# PGTNX06_ioexpander.net
KiCad netlist of a schematic drawn in EAGLE
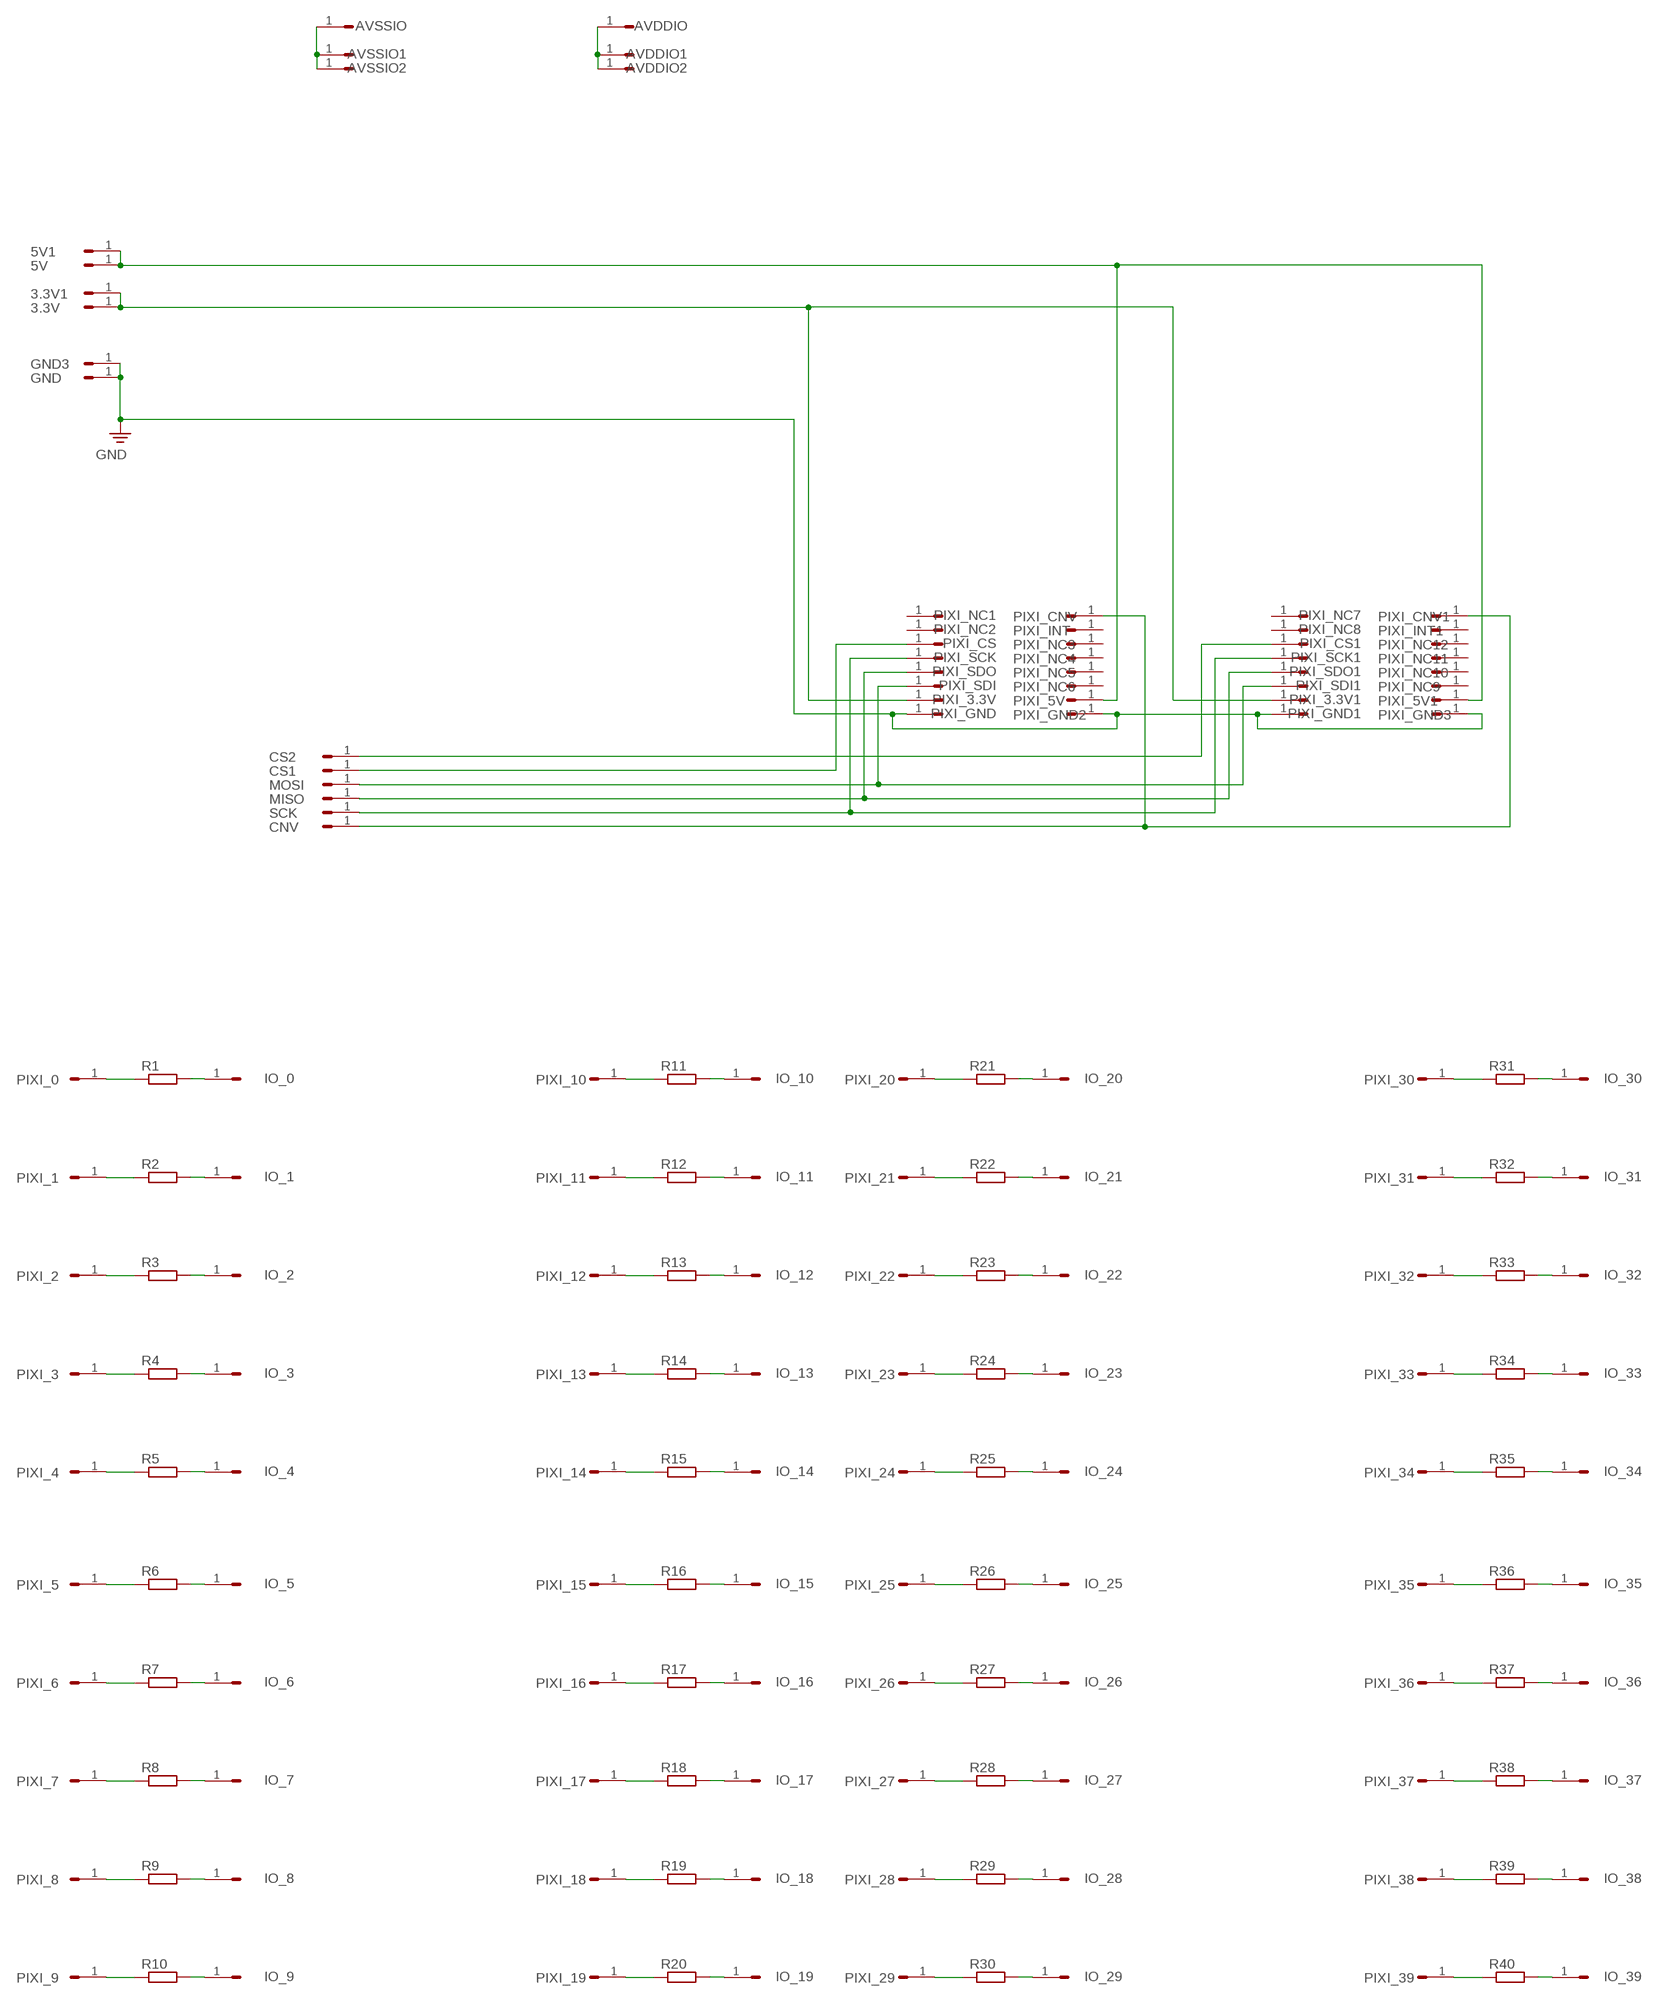
[diagram p0: schematic, sheet 1]

(export (version "E")
  (design (tool "Eeschema 10.0.6"))
  (components
    (comp (ref "3.3V")
      (value "HEADER/MALE/01")
      (footprint "eagle-import:HEADER_MALE_01")
      (fields (field (name "SPICEPREFIX") "X"))
      (libsource (lib "eagle-import") (part "HEADER/MALE/01"))
    )
    (comp (ref "3.3V1")
      (value "HEADER/MALE/01")
      (footprint "eagle-import:HEADER_MALE_01")
      (fields (field (name "SPICEPREFIX") "X"))
      (libsource (lib "eagle-import") (part "HEADER/MALE/01"))
    )
    (comp (ref "5V")
      (value "HEADER/MALE/01")
      (footprint "eagle-import:HEADER_MALE_01")
      (fields (field (name "SPICEPREFIX") "X"))
      (libsource (lib "eagle-import") (part "HEADER/MALE/01"))
    )
    (comp (ref "5V1")
      (value "HEADER/MALE/01")
      (footprint "eagle-import:HEADER_MALE_01")
      (fields (field (name "SPICEPREFIX") "X"))
      (libsource (lib "eagle-import") (part "HEADER/MALE/01"))
    )
    (comp (ref "AVDDIO")
      (value "HEADER/MALE/01")
      (footprint "eagle-import:HEADER_MALE_01")
      (fields (field (name "SPICEPREFIX") "X"))
      (libsource (lib "eagle-import") (part "HEADER/MALE/01"))
    )
    (comp (ref "AVDDIO1")
      (value "HEADER/MALE/01")
      (footprint "eagle-import:HEADER_MALE_01")
      (fields (field (name "SPICEPREFIX") "X"))
      (libsource (lib "eagle-import") (part "HEADER/MALE/01"))
    )
    (comp (ref "AVDDIO2")
      (value "HEADER/MALE/01")
      (footprint "eagle-import:HEADER_MALE_01")
      (fields (field (name "SPICEPREFIX") "X"))
      (libsource (lib "eagle-import") (part "HEADER/MALE/01"))
    )
    (comp (ref "AVSSIO")
      (value "HEADER/MALE/01")
      (footprint "eagle-import:HEADER_MALE_01")
      (fields (field (name "SPICEPREFIX") "X"))
      (libsource (lib "eagle-import") (part "HEADER/MALE/01"))
    )
    (comp (ref "AVSSIO1")
      (value "HEADER/MALE/01")
      (footprint "eagle-import:HEADER_MALE_01")
      (fields (field (name "SPICEPREFIX") "X"))
      (libsource (lib "eagle-import") (part "HEADER/MALE/01"))
    )
    (comp (ref "AVSSIO2")
      (value "HEADER/MALE/01")
      (footprint "eagle-import:HEADER_MALE_01")
      (fields (field (name "SPICEPREFIX") "X"))
      (libsource (lib "eagle-import") (part "HEADER/MALE/01"))
    )
    (comp (ref "CNV")
      (value "HEADER/MALE/01")
      (footprint "eagle-import:HEADER_MALE_01")
      (fields (field (name "SPICEPREFIX") "X"))
      (libsource (lib "eagle-import") (part "HEADER/MALE/01"))
    )
    (comp (ref "CS1")
      (value "HEADER/MALE/01")
      (footprint "eagle-import:HEADER_MALE_01")
      (fields (field (name "SPICEPREFIX") "X"))
      (libsource (lib "eagle-import") (part "HEADER/MALE/01"))
    )
    (comp (ref "CS2")
      (value "HEADER/MALE/01")
      (footprint "eagle-import:HEADER_MALE_01")
      (fields (field (name "SPICEPREFIX") "X"))
      (libsource (lib "eagle-import") (part "HEADER/MALE/01"))
    )
    (comp (ref "GND")
      (value "HEADER/MALE/01")
      (footprint "eagle-import:HEADER_MALE_01")
      (fields (field (name "SPICEPREFIX") "X"))
      (libsource (lib "eagle-import") (part "HEADER/MALE/01"))
    )
    (comp (ref "GND3")
      (value "HEADER/MALE/01")
      (footprint "eagle-import:HEADER_MALE_01")
      (fields (field (name "SPICEPREFIX") "X"))
      (libsource (lib "eagle-import") (part "HEADER/MALE/01"))
    )
    (comp (ref "IO_0")
      (value "HEADER/MALE/01")
      (footprint "eagle-import:HEADER_MALE_01")
      (fields (field (name "SPICEPREFIX") "X"))
      (libsource (lib "eagle-import") (part "HEADER/MALE/01"))
    )
    (comp (ref "IO_1")
      (value "HEADER/MALE/01")
      (footprint "eagle-import:HEADER_MALE_01")
      (fields (field (name "SPICEPREFIX") "X"))
      (libsource (lib "eagle-import") (part "HEADER/MALE/01"))
    )
    (comp (ref "IO_2")
      (value "HEADER/MALE/01")
      (footprint "eagle-import:HEADER_MALE_01")
      (fields (field (name "SPICEPREFIX") "X"))
      (libsource (lib "eagle-import") (part "HEADER/MALE/01"))
    )
    (comp (ref "IO_3")
      (value "HEADER/MALE/01")
      (footprint "eagle-import:HEADER_MALE_01")
      (fields (field (name "SPICEPREFIX") "X"))
      (libsource (lib "eagle-import") (part "HEADER/MALE/01"))
    )
    (comp (ref "IO_4")
      (value "HEADER/MALE/01")
      (footprint "eagle-import:HEADER_MALE_01")
      (fields (field (name "SPICEPREFIX") "X"))
      (libsource (lib "eagle-import") (part "HEADER/MALE/01"))
    )
    (comp (ref "IO_5")
      (value "HEADER/MALE/01")
      (footprint "eagle-import:HEADER_MALE_01")
      (fields (field (name "SPICEPREFIX") "X"))
      (libsource (lib "eagle-import") (part "HEADER/MALE/01"))
    )
    (comp (ref "IO_6")
      (value "HEADER/MALE/01")
      (footprint "eagle-import:HEADER_MALE_01")
      (fields (field (name "SPICEPREFIX") "X"))
      (libsource (lib "eagle-import") (part "HEADER/MALE/01"))
    )
    (comp (ref "IO_7")
      (value "HEADER/MALE/01")
      (footprint "eagle-import:HEADER_MALE_01")
      (fields (field (name "SPICEPREFIX") "X"))
      (libsource (lib "eagle-import") (part "HEADER/MALE/01"))
    )
    (comp (ref "IO_8")
      (value "HEADER/MALE/01")
      (footprint "eagle-import:HEADER_MALE_01")
      (fields (field (name "SPICEPREFIX") "X"))
      (libsource (lib "eagle-import") (part "HEADER/MALE/01"))
    )
    (comp (ref "IO_9")
      (value "HEADER/MALE/01")
      (footprint "eagle-import:HEADER_MALE_01")
      (fields (field (name "SPICEPREFIX") "X"))
      (libsource (lib "eagle-import") (part "HEADER/MALE/01"))
    )
    (comp (ref "IO_10")
      (value "HEADER/MALE/01")
      (footprint "eagle-import:HEADER_MALE_01")
      (fields (field (name "SPICEPREFIX") "X"))
      (libsource (lib "eagle-import") (part "HEADER/MALE/01"))
    )
    (comp (ref "IO_11")
      (value "HEADER/MALE/01")
      (footprint "eagle-import:HEADER_MALE_01")
      (fields (field (name "SPICEPREFIX") "X"))
      (libsource (lib "eagle-import") (part "HEADER/MALE/01"))
    )
    (comp (ref "IO_12")
      (value "HEADER/MALE/01")
      (footprint "eagle-import:HEADER_MALE_01")
      (fields (field (name "SPICEPREFIX") "X"))
      (libsource (lib "eagle-import") (part "HEADER/MALE/01"))
    )
    (comp (ref "IO_13")
      (value "HEADER/MALE/01")
      (footprint "eagle-import:HEADER_MALE_01")
      (fields (field (name "SPICEPREFIX") "X"))
      (libsource (lib "eagle-import") (part "HEADER/MALE/01"))
    )
    (comp (ref "IO_14")
      (value "HEADER/MALE/01")
      (footprint "eagle-import:HEADER_MALE_01")
      (fields (field (name "SPICEPREFIX") "X"))
      (libsource (lib "eagle-import") (part "HEADER/MALE/01"))
    )
    (comp (ref "IO_15")
      (value "HEADER/MALE/01")
      (footprint "eagle-import:HEADER_MALE_01")
      (fields (field (name "SPICEPREFIX") "X"))
      (libsource (lib "eagle-import") (part "HEADER/MALE/01"))
    )
    (comp (ref "IO_16")
      (value "HEADER/MALE/01")
      (footprint "eagle-import:HEADER_MALE_01")
      (fields (field (name "SPICEPREFIX") "X"))
      (libsource (lib "eagle-import") (part "HEADER/MALE/01"))
    )
    (comp (ref "IO_17")
      (value "HEADER/MALE/01")
      (footprint "eagle-import:HEADER_MALE_01")
      (fields (field (name "SPICEPREFIX") "X"))
      (libsource (lib "eagle-import") (part "HEADER/MALE/01"))
    )
    (comp (ref "IO_18")
      (value "HEADER/MALE/01")
      (footprint "eagle-import:HEADER_MALE_01")
      (fields (field (name "SPICEPREFIX") "X"))
      (libsource (lib "eagle-import") (part "HEADER/MALE/01"))
    )
    (comp (ref "IO_19")
      (value "HEADER/MALE/01")
      (footprint "eagle-import:HEADER_MALE_01")
      (fields (field (name "SPICEPREFIX") "X"))
      (libsource (lib "eagle-import") (part "HEADER/MALE/01"))
    )
    (comp (ref "IO_20")
      (value "HEADER/MALE/01")
      (footprint "eagle-import:HEADER_MALE_01")
      (fields (field (name "SPICEPREFIX") "X"))
      (libsource (lib "eagle-import") (part "HEADER/MALE/01"))
    )
    (comp (ref "IO_21")
      (value "HEADER/MALE/01")
      (footprint "eagle-import:HEADER_MALE_01")
      (fields (field (name "SPICEPREFIX") "X"))
      (libsource (lib "eagle-import") (part "HEADER/MALE/01"))
    )
    (comp (ref "IO_22")
      (value "HEADER/MALE/01")
      (footprint "eagle-import:HEADER_MALE_01")
      (fields (field (name "SPICEPREFIX") "X"))
      (libsource (lib "eagle-import") (part "HEADER/MALE/01"))
    )
    (comp (ref "IO_23")
      (value "HEADER/MALE/01")
      (footprint "eagle-import:HEADER_MALE_01")
      (fields (field (name "SPICEPREFIX") "X"))
      (libsource (lib "eagle-import") (part "HEADER/MALE/01"))
    )
    (comp (ref "IO_24")
      (value "HEADER/MALE/01")
      (footprint "eagle-import:HEADER_MALE_01")
      (fields (field (name "SPICEPREFIX") "X"))
      (libsource (lib "eagle-import") (part "HEADER/MALE/01"))
    )
    (comp (ref "IO_25")
      (value "HEADER/MALE/01")
      (footprint "eagle-import:HEADER_MALE_01")
      (fields (field (name "SPICEPREFIX") "X"))
      (libsource (lib "eagle-import") (part "HEADER/MALE/01"))
    )
    (comp (ref "IO_26")
      (value "HEADER/MALE/01")
      (footprint "eagle-import:HEADER_MALE_01")
      (fields (field (name "SPICEPREFIX") "X"))
      (libsource (lib "eagle-import") (part "HEADER/MALE/01"))
    )
    (comp (ref "IO_27")
      (value "HEADER/MALE/01")
      (footprint "eagle-import:HEADER_MALE_01")
      (fields (field (name "SPICEPREFIX") "X"))
      (libsource (lib "eagle-import") (part "HEADER/MALE/01"))
    )
    (comp (ref "IO_28")
      (value "HEADER/MALE/01")
      (footprint "eagle-import:HEADER_MALE_01")
      (fields (field (name "SPICEPREFIX") "X"))
      (libsource (lib "eagle-import") (part "HEADER/MALE/01"))
    )
    (comp (ref "IO_29")
      (value "HEADER/MALE/01")
      (footprint "eagle-import:HEADER_MALE_01")
      (fields (field (name "SPICEPREFIX") "X"))
      (libsource (lib "eagle-import") (part "HEADER/MALE/01"))
    )
    (comp (ref "IO_30")
      (value "HEADER/MALE/01")
      (footprint "eagle-import:HEADER_MALE_01")
      (fields (field (name "SPICEPREFIX") "X"))
      (libsource (lib "eagle-import") (part "HEADER/MALE/01"))
    )
    (comp (ref "IO_31")
      (value "HEADER/MALE/01")
      (footprint "eagle-import:HEADER_MALE_01")
      (fields (field (name "SPICEPREFIX") "X"))
      (libsource (lib "eagle-import") (part "HEADER/MALE/01"))
    )
    (comp (ref "IO_32")
      (value "HEADER/MALE/01")
      (footprint "eagle-import:HEADER_MALE_01")
      (fields (field (name "SPICEPREFIX") "X"))
      (libsource (lib "eagle-import") (part "HEADER/MALE/01"))
    )
    (comp (ref "IO_33")
      (value "HEADER/MALE/01")
      (footprint "eagle-import:HEADER_MALE_01")
      (fields (field (name "SPICEPREFIX") "X"))
      (libsource (lib "eagle-import") (part "HEADER/MALE/01"))
    )
    (comp (ref "IO_34")
      (value "HEADER/MALE/01")
      (footprint "eagle-import:HEADER_MALE_01")
      (fields (field (name "SPICEPREFIX") "X"))
      (libsource (lib "eagle-import") (part "HEADER/MALE/01"))
    )
    (comp (ref "IO_35")
      (value "HEADER/MALE/01")
      (footprint "eagle-import:HEADER_MALE_01")
      (fields (field (name "SPICEPREFIX") "X"))
      (libsource (lib "eagle-import") (part "HEADER/MALE/01"))
    )
    (comp (ref "IO_36")
      (value "HEADER/MALE/01")
      (footprint "eagle-import:HEADER_MALE_01")
      (fields (field (name "SPICEPREFIX") "X"))
      (libsource (lib "eagle-import") (part "HEADER/MALE/01"))
    )
    (comp (ref "IO_37")
      (value "HEADER/MALE/01")
      (footprint "eagle-import:HEADER_MALE_01")
      (fields (field (name "SPICEPREFIX") "X"))
      (libsource (lib "eagle-import") (part "HEADER/MALE/01"))
    )
    (comp (ref "IO_38")
      (value "HEADER/MALE/01")
      (footprint "eagle-import:HEADER_MALE_01")
      (fields (field (name "SPICEPREFIX") "X"))
      (libsource (lib "eagle-import") (part "HEADER/MALE/01"))
    )
    (comp (ref "IO_39")
      (value "HEADER/MALE/01")
      (footprint "eagle-import:HEADER_MALE_01")
      (fields (field (name "SPICEPREFIX") "X"))
      (libsource (lib "eagle-import") (part "HEADER/MALE/01"))
    )
    (comp (ref "MISO")
      (value "HEADER/MALE/01")
      (footprint "eagle-import:HEADER_MALE_01")
      (fields (field (name "SPICEPREFIX") "X"))
      (libsource (lib "eagle-import") (part "HEADER/MALE/01"))
    )
    (comp (ref "MOSI")
      (value "HEADER/MALE/01")
      (footprint "eagle-import:HEADER_MALE_01")
      (fields (field (name "SPICEPREFIX") "X"))
      (libsource (lib "eagle-import") (part "HEADER/MALE/01"))
    )
    (comp (ref "PIXI_0")
      (value "HEADER/MALE/01")
      (footprint "eagle-import:HEADER_MALE_01")
      (fields (field (name "SPICEPREFIX") "X"))
      (libsource (lib "eagle-import") (part "HEADER/MALE/01"))
    )
    (comp (ref "PIXI_1")
      (value "HEADER/MALE/01")
      (footprint "eagle-import:HEADER_MALE_01")
      (fields (field (name "SPICEPREFIX") "X"))
      (libsource (lib "eagle-import") (part "HEADER/MALE/01"))
    )
    (comp (ref "PIXI_2")
      (value "HEADER/MALE/01")
      (footprint "eagle-import:HEADER_MALE_01")
      (fields (field (name "SPICEPREFIX") "X"))
      (libsource (lib "eagle-import") (part "HEADER/MALE/01"))
    )
    (comp (ref "PIXI_3")
      (value "HEADER/MALE/01")
      (footprint "eagle-import:HEADER_MALE_01")
      (fields (field (name "SPICEPREFIX") "X"))
      (libsource (lib "eagle-import") (part "HEADER/MALE/01"))
    )
    (comp (ref "PIXI_3.3V")
      (value "HEADER/MALE/01")
      (footprint "eagle-import:HEADER_MALE_01")
      (fields (field (name "SPICEPREFIX") "X"))
      (libsource (lib "eagle-import") (part "HEADER/MALE/01"))
    )
    (comp (ref "PIXI_3.3V1")
      (value "HEADER/MALE/01")
      (footprint "eagle-import:HEADER_MALE_01")
      (fields (field (name "SPICEPREFIX") "X"))
      (libsource (lib "eagle-import") (part "HEADER/MALE/01"))
    )
    (comp (ref "PIXI_4")
      (value "HEADER/MALE/01")
      (footprint "eagle-import:HEADER_MALE_01")
      (fields (field (name "SPICEPREFIX") "X"))
      (libsource (lib "eagle-import") (part "HEADER/MALE/01"))
    )
    (comp (ref "PIXI_5")
      (value "HEADER/MALE/01")
      (footprint "eagle-import:HEADER_MALE_01")
      (fields (field (name "SPICEPREFIX") "X"))
      (libsource (lib "eagle-import") (part "HEADER/MALE/01"))
    )
    (comp (ref "PIXI_5V")
      (value "HEADER/MALE/01")
      (footprint "eagle-import:HEADER_MALE_01")
      (fields (field (name "SPICEPREFIX") "X"))
      (libsource (lib "eagle-import") (part "HEADER/MALE/01"))
    )
    (comp (ref "PIXI_5V1")
      (value "HEADER/MALE/01")
      (footprint "eagle-import:HEADER_MALE_01")
      (fields (field (name "SPICEPREFIX") "X"))
      (libsource (lib "eagle-import") (part "HEADER/MALE/01"))
    )
    (comp (ref "PIXI_6")
      (value "HEADER/MALE/01")
      (footprint "eagle-import:HEADER_MALE_01")
      (fields (field (name "SPICEPREFIX") "X"))
      (libsource (lib "eagle-import") (part "HEADER/MALE/01"))
    )
    (comp (ref "PIXI_7")
      (value "HEADER/MALE/01")
      (footprint "eagle-import:HEADER_MALE_01")
      (fields (field (name "SPICEPREFIX") "X"))
      (libsource (lib "eagle-import") (part "HEADER/MALE/01"))
    )
    (comp (ref "PIXI_8")
      (value "HEADER/MALE/01")
      (footprint "eagle-import:HEADER_MALE_01")
      (fields (field (name "SPICEPREFIX") "X"))
      (libsource (lib "eagle-import") (part "HEADER/MALE/01"))
    )
    (comp (ref "PIXI_9")
      (value "HEADER/MALE/01")
      (footprint "eagle-import:HEADER_MALE_01")
      (fields (field (name "SPICEPREFIX") "X"))
      (libsource (lib "eagle-import") (part "HEADER/MALE/01"))
    )
    (comp (ref "PIXI_10")
      (value "HEADER/MALE/01")
      (footprint "eagle-import:HEADER_MALE_01")
      (fields (field (name "SPICEPREFIX") "X"))
      (libsource (lib "eagle-import") (part "HEADER/MALE/01"))
    )
    (comp (ref "PIXI_11")
      (value "HEADER/MALE/01")
      (footprint "eagle-import:HEADER_MALE_01")
      (fields (field (name "SPICEPREFIX") "X"))
      (libsource (lib "eagle-import") (part "HEADER/MALE/01"))
    )
    (comp (ref "PIXI_12")
      (value "HEADER/MALE/01")
      (footprint "eagle-import:HEADER_MALE_01")
      (fields (field (name "SPICEPREFIX") "X"))
      (libsource (lib "eagle-import") (part "HEADER/MALE/01"))
    )
    (comp (ref "PIXI_13")
      (value "HEADER/MALE/01")
      (footprint "eagle-import:HEADER_MALE_01")
      (fields (field (name "SPICEPREFIX") "X"))
      (libsource (lib "eagle-import") (part "HEADER/MALE/01"))
    )
    (comp (ref "PIXI_14")
      (value "HEADER/MALE/01")
      (footprint "eagle-import:HEADER_MALE_01")
      (fields (field (name "SPICEPREFIX") "X"))
      (libsource (lib "eagle-import") (part "HEADER/MALE/01"))
    )
    (comp (ref "PIXI_15")
      (value "HEADER/MALE/01")
      (footprint "eagle-import:HEADER_MALE_01")
      (fields (field (name "SPICEPREFIX") "X"))
      (libsource (lib "eagle-import") (part "HEADER/MALE/01"))
    )
    (comp (ref "PIXI_16")
      (value "HEADER/MALE/01")
      (footprint "eagle-import:HEADER_MALE_01")
      (fields (field (name "SPICEPREFIX") "X"))
      (libsource (lib "eagle-import") (part "HEADER/MALE/01"))
    )
    (comp (ref "PIXI_17")
      (value "HEADER/MALE/01")
      (footprint "eagle-import:HEADER_MALE_01")
      (fields (field (name "SPICEPREFIX") "X"))
      (libsource (lib "eagle-import") (part "HEADER/MALE/01"))
    )
    (comp (ref "PIXI_18")
      (value "HEADER/MALE/01")
      (footprint "eagle-import:HEADER_MALE_01")
      (fields (field (name "SPICEPREFIX") "X"))
      (libsource (lib "eagle-import") (part "HEADER/MALE/01"))
    )
    (comp (ref "PIXI_19")
      (value "HEADER/MALE/01")
      (footprint "eagle-import:HEADER_MALE_01")
      (fields (field (name "SPICEPREFIX") "X"))
      (libsource (lib "eagle-import") (part "HEADER/MALE/01"))
    )
    (comp (ref "PIXI_20")
      (value "HEADER/MALE/01")
      (footprint "eagle-import:HEADER_MALE_01")
      (fields (field (name "SPICEPREFIX") "X"))
      (libsource (lib "eagle-import") (part "HEADER/MALE/01"))
    )
    (comp (ref "PIXI_21")
      (value "HEADER/MALE/01")
      (footprint "eagle-import:HEADER_MALE_01")
      (fields (field (name "SPICEPREFIX") "X"))
      (libsource (lib "eagle-import") (part "HEADER/MALE/01"))
    )
    (comp (ref "PIXI_22")
      (value "HEADER/MALE/01")
      (footprint "eagle-import:HEADER_MALE_01")
      (fields (field (name "SPICEPREFIX") "X"))
      (libsource (lib "eagle-import") (part "HEADER/MALE/01"))
    )
    (comp (ref "PIXI_23")
      (value "HEADER/MALE/01")
      (footprint "eagle-import:HEADER_MALE_01")
      (fields (field (name "SPICEPREFIX") "X"))
      (libsource (lib "eagle-import") (part "HEADER/MALE/01"))
    )
    (comp (ref "PIXI_24")
      (value "HEADER/MALE/01")
      (footprint "eagle-import:HEADER_MALE_01")
      (fields (field (name "SPICEPREFIX") "X"))
      (libsource (lib "eagle-import") (part "HEADER/MALE/01"))
    )
    (comp (ref "PIXI_25")
      (value "HEADER/MALE/01")
      (footprint "eagle-import:HEADER_MALE_01")
      (fields (field (name "SPICEPREFIX") "X"))
      (libsource (lib "eagle-import") (part "HEADER/MALE/01"))
    )
    (comp (ref "PIXI_26")
      (value "HEADER/MALE/01")
      (footprint "eagle-import:HEADER_MALE_01")
      (fields (field (name "SPICEPREFIX") "X"))
      (libsource (lib "eagle-import") (part "HEADER/MALE/01"))
    )
    (comp (ref "PIXI_27")
      (value "HEADER/MALE/01")
      (footprint "eagle-import:HEADER_MALE_01")
      (fields (field (name "SPICEPREFIX") "X"))
      (libsource (lib "eagle-import") (part "HEADER/MALE/01"))
    )
    (comp (ref "PIXI_28")
      (value "HEADER/MALE/01")
      (footprint "eagle-import:HEADER_MALE_01")
      (fields (field (name "SPICEPREFIX") "X"))
      (libsource (lib "eagle-import") (part "HEADER/MALE/01"))
    )
    (comp (ref "PIXI_29")
      (value "HEADER/MALE/01")
      (footprint "eagle-import:HEADER_MALE_01")
      (fields (field (name "SPICEPREFIX") "X"))
      (libsource (lib "eagle-import") (part "HEADER/MALE/01"))
    )
    (comp (ref "PIXI_30")
      (value "HEADER/MALE/01")
      (footprint "eagle-import:HEADER_MALE_01")
      (fields (field (name "SPICEPREFIX") "X"))
      (libsource (lib "eagle-import") (part "HEADER/MALE/01"))
    )
    (comp (ref "PIXI_31")
      (value "HEADER/MALE/01")
      (footprint "eagle-import:HEADER_MALE_01")
      (fields (field (name "SPICEPREFIX") "X"))
      (libsource (lib "eagle-import") (part "HEADER/MALE/01"))
    )
    (comp (ref "PIXI_32")
      (value "HEADER/MALE/01")
      (footprint "eagle-import:HEADER_MALE_01")
      (fields (field (name "SPICEPREFIX") "X"))
      (libsource (lib "eagle-import") (part "HEADER/MALE/01"))
    )
    (comp (ref "PIXI_33")
      (value "HEADER/MALE/01")
      (footprint "eagle-import:HEADER_MALE_01")
      (fields (field (name "SPICEPREFIX") "X"))
      (libsource (lib "eagle-import") (part "HEADER/MALE/01"))
    )
    (comp (ref "PIXI_34")
      (value "HEADER/MALE/01")
      (footprint "eagle-import:HEADER_MALE_01")
      (fields (field (name "SPICEPREFIX") "X"))
      (libsource (lib "eagle-import") (part "HEADER/MALE/01"))
    )
    (comp (ref "PIXI_35")
      (value "HEADER/MALE/01")
      (footprint "eagle-import:HEADER_MALE_01")
      (fields (field (name "SPICEPREFIX") "X"))
      (libsource (lib "eagle-import") (part "HEADER/MALE/01"))
    )
    (comp (ref "PIXI_36")
      (value "HEADER/MALE/01")
      (footprint "eagle-import:HEADER_MALE_01")
      (fields (field (name "SPICEPREFIX") "X"))
      (libsource (lib "eagle-import") (part "HEADER/MALE/01"))
    )
    (comp (ref "PIXI_37")
      (value "HEADER/MALE/01")
      (footprint "eagle-import:HEADER_MALE_01")
      (fields (field (name "SPICEPREFIX") "X"))
      (libsource (lib "eagle-import") (part "HEADER/MALE/01"))
    )
    (comp (ref "PIXI_38")
      (value "HEADER/MALE/01")
      (footprint "eagle-import:HEADER_MALE_01")
      (fields (field (name "SPICEPREFIX") "X"))
      (libsource (lib "eagle-import") (part "HEADER/MALE/01"))
    )
    (comp (ref "PIXI_39")
      (value "HEADER/MALE/01")
      (footprint "eagle-import:HEADER_MALE_01")
      (fields (field (name "SPICEPREFIX") "X"))
      (libsource (lib "eagle-import") (part "HEADER/MALE/01"))
    )
    (comp (ref "PIXI_CNV")
      (value "HEADER/MALE/01")
      (footprint "eagle-import:HEADER_MALE_01")
      (fields (field (name "SPICEPREFIX") "X"))
      (libsource (lib "eagle-import") (part "HEADER/MALE/01"))
    )
    (comp (ref "PIXI_CNV1")
      (value "HEADER/MALE/01")
      (footprint "eagle-import:HEADER_MALE_01")
      (fields (field (name "SPICEPREFIX") "X"))
      (libsource (lib "eagle-import") (part "HEADER/MALE/01"))
    )
    (comp (ref "PIXI_CS")
      (value "HEADER/MALE/01")
      (footprint "eagle-import:HEADER_MALE_01")
      (fields (field (name "SPICEPREFIX") "X"))
      (libsource (lib "eagle-import") (part "HEADER/MALE/01"))
    )
    (comp (ref "PIXI_CS1")
      (value "HEADER/MALE/01")
      (footprint "eagle-import:HEADER_MALE_01")
      (fields (field (name "SPICEPREFIX") "X"))
      (libsource (lib "eagle-import") (part "HEADER/MALE/01"))
    )
    (comp (ref "PIXI_GND")
      (value "HEADER/MALE/01")
      (footprint "eagle-import:HEADER_MALE_01")
      (fields (field (name "SPICEPREFIX") "X"))
      (libsource (lib "eagle-import") (part "HEADER/MALE/01"))
    )
    (comp (ref "PIXI_GND1")
      (value "HEADER/MALE/01")
      (footprint "eagle-import:HEADER_MALE_01")
      (fields (field (name "SPICEPREFIX") "X"))
      (libsource (lib "eagle-import") (part "HEADER/MALE/01"))
    )
    (comp (ref "PIXI_GND2")
      (value "HEADER/MALE/01")
      (footprint "eagle-import:HEADER_MALE_01")
      (fields (field (name "SPICEPREFIX") "X"))
      (libsource (lib "eagle-import") (part "HEADER/MALE/01"))
    )
    (comp (ref "PIXI_GND3")
      (value "HEADER/MALE/01")
      (footprint "eagle-import:HEADER_MALE_01")
      (fields (field (name "SPICEPREFIX") "X"))
      (libsource (lib "eagle-import") (part "HEADER/MALE/01"))
    )
    (comp (ref "PIXI_INT")
      (value "HEADER/MALE/01")
      (footprint "eagle-import:HEADER_MALE_01")
      (fields (field (name "SPICEPREFIX") "X"))
      (libsource (lib "eagle-import") (part "HEADER/MALE/01"))
    )
    (comp (ref "PIXI_INT1")
      (value "HEADER/MALE/01")
      (footprint "eagle-import:HEADER_MALE_01")
      (fields (field (name "SPICEPREFIX") "X"))
      (libsource (lib "eagle-import") (part "HEADER/MALE/01"))
    )
    (comp (ref "PIXI_NC1")
      (value "HEADER/MALE/01")
      (footprint "eagle-import:HEADER_MALE_01")
      (fields (field (name "SPICEPREFIX") "X"))
      (libsource (lib "eagle-import") (part "HEADER/MALE/01"))
    )
    (comp (ref "PIXI_NC2")
      (value "HEADER/MALE/01")
      (footprint "eagle-import:HEADER_MALE_01")
      (fields (field (name "SPICEPREFIX") "X"))
      (libsource (lib "eagle-import") (part "HEADER/MALE/01"))
    )
    (comp (ref "PIXI_NC3")
      (value "HEADER/MALE/01")
      (footprint "eagle-import:HEADER_MALE_01")
      (fields (field (name "SPICEPREFIX") "X"))
      (libsource (lib "eagle-import") (part "HEADER/MALE/01"))
    )
    (comp (ref "PIXI_NC4")
      (value "HEADER/MALE/01")
      (footprint "eagle-import:HEADER_MALE_01")
      (fields (field (name "SPICEPREFIX") "X"))
      (libsource (lib "eagle-import") (part "HEADER/MALE/01"))
    )
    (comp (ref "PIXI_NC5")
      (value "HEADER/MALE/01")
      (footprint "eagle-import:HEADER_MALE_01")
      (fields (field (name "SPICEPREFIX") "X"))
      (libsource (lib "eagle-import") (part "HEADER/MALE/01"))
    )
    (comp (ref "PIXI_NC6")
      (value "HEADER/MALE/01")
      (footprint "eagle-import:HEADER_MALE_01")
      (fields (field (name "SPICEPREFIX") "X"))
      (libsource (lib "eagle-import") (part "HEADER/MALE/01"))
    )
    (comp (ref "PIXI_NC7")
      (value "HEADER/MALE/01")
      (footprint "eagle-import:HEADER_MALE_01")
      (fields (field (name "SPICEPREFIX") "X"))
      (libsource (lib "eagle-import") (part "HEADER/MALE/01"))
    )
    (comp (ref "PIXI_NC8")
      (value "HEADER/MALE/01")
      (footprint "eagle-import:HEADER_MALE_01")
      (fields (field (name "SPICEPREFIX") "X"))
      (libsource (lib "eagle-import") (part "HEADER/MALE/01"))
    )
    (comp (ref "PIXI_NC9")
      (value "HEADER/MALE/01")
      (footprint "eagle-import:HEADER_MALE_01")
      (fields (field (name "SPICEPREFIX") "X"))
      (libsource (lib "eagle-import") (part "HEADER/MALE/01"))
    )
    (comp (ref "PIXI_NC10")
      (value "HEADER/MALE/01")
      (footprint "eagle-import:HEADER_MALE_01")
      (fields (field (name "SPICEPREFIX") "X"))
      (libsource (lib "eagle-import") (part "HEADER/MALE/01"))
    )
    (comp (ref "PIXI_NC11")
      (value "HEADER/MALE/01")
      (footprint "eagle-import:HEADER_MALE_01")
      (fields (field (name "SPICEPREFIX") "X"))
      (libsource (lib "eagle-import") (part "HEADER/MALE/01"))
    )
    (comp (ref "PIXI_NC12")
      (value "HEADER/MALE/01")
      (footprint "eagle-import:HEADER_MALE_01")
      (fields (field (name "SPICEPREFIX") "X"))
      (libsource (lib "eagle-import") (part "HEADER/MALE/01"))
    )
    (comp (ref "PIXI_SCK")
      (value "HEADER/MALE/01")
      (footprint "eagle-import:HEADER_MALE_01")
      (fields (field (name "SPICEPREFIX") "X"))
      (libsource (lib "eagle-import") (part "HEADER/MALE/01"))
    )
    (comp (ref "PIXI_SCK1")
      (value "HEADER/MALE/01")
      (footprint "eagle-import:HEADER_MALE_01")
      (fields (field (name "SPICEPREFIX") "X"))
      (libsource (lib "eagle-import") (part "HEADER/MALE/01"))
    )
    (comp (ref "PIXI_SDI")
      (value "HEADER/MALE/01")
      (footprint "eagle-import:HEADER_MALE_01")
      (fields (field (name "SPICEPREFIX") "X"))
      (libsource (lib "eagle-import") (part "HEADER/MALE/01"))
    )
    (comp (ref "PIXI_SDI1")
      (value "HEADER/MALE/01")
      (footprint "eagle-import:HEADER_MALE_01")
      (fields (field (name "SPICEPREFIX") "X"))
      (libsource (lib "eagle-import") (part "HEADER/MALE/01"))
    )
    (comp (ref "PIXI_SDO")
      (value "HEADER/MALE/01")
      (footprint "eagle-import:HEADER_MALE_01")
      (fields (field (name "SPICEPREFIX") "X"))
      (libsource (lib "eagle-import") (part "HEADER/MALE/01"))
    )
    (comp (ref "PIXI_SDO1")
      (value "HEADER/MALE/01")
      (footprint "eagle-import:HEADER_MALE_01")
      (fields (field (name "SPICEPREFIX") "X"))
      (libsource (lib "eagle-import") (part "HEADER/MALE/01"))
    )
    (comp (ref "R1")
      (value "RESISTORRESISTOR/UPRIGHT/7.5")
      (footprint "eagle-import:RESISTOR_7.5")
      (libsource (lib "eagle-import") (part "RESISTORRESISTOR/UPRIGHT/7.5"))
    )
    (comp (ref "R2")
      (value "RESISTORRESISTOR/UPRIGHT/7.5")
      (footprint "eagle-import:RESISTOR_7.5")
      (libsource (lib "eagle-import") (part "RESISTORRESISTOR/UPRIGHT/7.5"))
    )
    (comp (ref "R3")
      (value "RESISTORRESISTOR/UPRIGHT/7.5")
      (footprint "eagle-import:RESISTOR_7.5")
      (libsource (lib "eagle-import") (part "RESISTORRESISTOR/UPRIGHT/7.5"))
    )
    (comp (ref "R4")
      (value "RESISTORRESISTOR/UPRIGHT/7.5")
      (footprint "eagle-import:RESISTOR_7.5")
      (libsource (lib "eagle-import") (part "RESISTORRESISTOR/UPRIGHT/7.5"))
    )
    (comp (ref "R5")
      (value "RESISTORRESISTOR/UPRIGHT/7.5")
      (footprint "eagle-import:RESISTOR_7.5")
      (libsource (lib "eagle-import") (part "RESISTORRESISTOR/UPRIGHT/7.5"))
    )
    (comp (ref "R6")
      (value "RESISTORRESISTOR/UPRIGHT/7.5")
      (footprint "eagle-import:RESISTOR_7.5")
      (libsource (lib "eagle-import") (part "RESISTORRESISTOR/UPRIGHT/7.5"))
    )
    (comp (ref "R7")
      (value "RESISTORRESISTOR/UPRIGHT/7.5")
      (footprint "eagle-import:RESISTOR_7.5")
      (libsource (lib "eagle-import") (part "RESISTORRESISTOR/UPRIGHT/7.5"))
    )
    (comp (ref "R8")
      (value "RESISTORRESISTOR/UPRIGHT/7.5")
      (footprint "eagle-import:RESISTOR_7.5")
      (libsource (lib "eagle-import") (part "RESISTORRESISTOR/UPRIGHT/7.5"))
    )
    (comp (ref "R9")
      (value "RESISTORRESISTOR/UPRIGHT/7.5")
      (footprint "eagle-import:RESISTOR_7.5")
      (libsource (lib "eagle-import") (part "RESISTORRESISTOR/UPRIGHT/7.5"))
    )
    (comp (ref "R10")
      (value "RESISTORRESISTOR/UPRIGHT/7.5")
      (footprint "eagle-import:RESISTOR_7.5")
      (libsource (lib "eagle-import") (part "RESISTORRESISTOR/UPRIGHT/7.5"))
    )
    (comp (ref "R11")
      (value "RESISTORRESISTOR/UPRIGHT/7.5")
      (footprint "eagle-import:RESISTOR_7.5")
      (libsource (lib "eagle-import") (part "RESISTORRESISTOR/UPRIGHT/7.5"))
    )
    (comp (ref "R12")
      (value "RESISTORRESISTOR/UPRIGHT/7.5")
      (footprint "eagle-import:RESISTOR_7.5")
      (libsource (lib "eagle-import") (part "RESISTORRESISTOR/UPRIGHT/7.5"))
    )
    (comp (ref "R13")
      (value "RESISTORRESISTOR/UPRIGHT/7.5")
      (footprint "eagle-import:RESISTOR_7.5")
      (libsource (lib "eagle-import") (part "RESISTORRESISTOR/UPRIGHT/7.5"))
    )
    (comp (ref "R14")
      (value "RESISTORRESISTOR/UPRIGHT/7.5")
      (footprint "eagle-import:RESISTOR_7.5")
      (libsource (lib "eagle-import") (part "RESISTORRESISTOR/UPRIGHT/7.5"))
    )
    (comp (ref "R15")
      (value "RESISTORRESISTOR/UPRIGHT/7.5")
      (footprint "eagle-import:RESISTOR_7.5")
      (libsource (lib "eagle-import") (part "RESISTORRESISTOR/UPRIGHT/7.5"))
    )
    (comp (ref "R16")
      (value "RESISTORRESISTOR/UPRIGHT/7.5")
      (footprint "eagle-import:RESISTOR_7.5")
      (libsource (lib "eagle-import") (part "RESISTORRESISTOR/UPRIGHT/7.5"))
    )
    (comp (ref "R17")
      (value "RESISTORRESISTOR/UPRIGHT/7.5")
      (footprint "eagle-import:RESISTOR_7.5")
      (libsource (lib "eagle-import") (part "RESISTORRESISTOR/UPRIGHT/7.5"))
    )
    (comp (ref "R18")
      (value "RESISTORRESISTOR/UPRIGHT/7.5")
      (footprint "eagle-import:RESISTOR_7.5")
      (libsource (lib "eagle-import") (part "RESISTORRESISTOR/UPRIGHT/7.5"))
    )
    (comp (ref "R19")
      (value "RESISTORRESISTOR/UPRIGHT/7.5")
      (footprint "eagle-import:RESISTOR_7.5")
      (libsource (lib "eagle-import") (part "RESISTORRESISTOR/UPRIGHT/7.5"))
    )
    (comp (ref "R20")
      (value "RESISTORRESISTOR/UPRIGHT/7.5")
      (footprint "eagle-import:RESISTOR_7.5")
      (libsource (lib "eagle-import") (part "RESISTORRESISTOR/UPRIGHT/7.5"))
    )
    (comp (ref "R21")
      (value "RESISTORRESISTOR/UPRIGHT/7.5")
      (footprint "eagle-import:RESISTOR_7.5")
      (libsource (lib "eagle-import") (part "RESISTORRESISTOR/UPRIGHT/7.5"))
    )
    (comp (ref "R22")
      (value "RESISTORRESISTOR/UPRIGHT/7.5")
      (footprint "eagle-import:RESISTOR_7.5")
      (libsource (lib "eagle-import") (part "RESISTORRESISTOR/UPRIGHT/7.5"))
    )
    (comp (ref "R23")
      (value "RESISTORRESISTOR/UPRIGHT/7.5")
      (footprint "eagle-import:RESISTOR_7.5")
      (libsource (lib "eagle-import") (part "RESISTORRESISTOR/UPRIGHT/7.5"))
    )
    (comp (ref "R24")
      (value "RESISTORRESISTOR/UPRIGHT/7.5")
      (footprint "eagle-import:RESISTOR_7.5")
      (libsource (lib "eagle-import") (part "RESISTORRESISTOR/UPRIGHT/7.5"))
    )
    (comp (ref "R25")
      (value "RESISTORRESISTOR/UPRIGHT/7.5")
      (footprint "eagle-import:RESISTOR_7.5")
      (libsource (lib "eagle-import") (part "RESISTORRESISTOR/UPRIGHT/7.5"))
    )
    (comp (ref "R26")
      (value "RESISTORRESISTOR/UPRIGHT/7.5")
      (footprint "eagle-import:RESISTOR_7.5")
      (libsource (lib "eagle-import") (part "RESISTORRESISTOR/UPRIGHT/7.5"))
    )
    (comp (ref "R27")
      (value "RESISTORRESISTOR/UPRIGHT/7.5")
      (footprint "eagle-import:RESISTOR_7.5")
      (libsource (lib "eagle-import") (part "RESISTORRESISTOR/UPRIGHT/7.5"))
    )
    (comp (ref "R28")
      (value "RESISTORRESISTOR/UPRIGHT/7.5")
      (footprint "eagle-import:RESISTOR_7.5")
      (libsource (lib "eagle-import") (part "RESISTORRESISTOR/UPRIGHT/7.5"))
    )
    (comp (ref "R29")
      (value "RESISTORRESISTOR/UPRIGHT/7.5")
      (footprint "eagle-import:RESISTOR_7.5")
      (libsource (lib "eagle-import") (part "RESISTORRESISTOR/UPRIGHT/7.5"))
    )
    (comp (ref "R30")
      (value "RESISTORRESISTOR/UPRIGHT/7.5")
      (footprint "eagle-import:RESISTOR_7.5")
      (libsource (lib "eagle-import") (part "RESISTORRESISTOR/UPRIGHT/7.5"))
    )
    (comp (ref "R31")
      (value "RESISTORRESISTOR/UPRIGHT/7.5")
      (footprint "eagle-import:RESISTOR_7.5")
      (libsource (lib "eagle-import") (part "RESISTORRESISTOR/UPRIGHT/7.5"))
    )
    (comp (ref "R32")
      (value "RESISTORRESISTOR/UPRIGHT/7.5")
      (footprint "eagle-import:RESISTOR_7.5")
      (libsource (lib "eagle-import") (part "RESISTORRESISTOR/UPRIGHT/7.5"))
    )
    (comp (ref "R33")
      (value "RESISTORRESISTOR/UPRIGHT/7.5")
      (footprint "eagle-import:RESISTOR_7.5")
      (libsource (lib "eagle-import") (part "RESISTORRESISTOR/UPRIGHT/7.5"))
    )
    (comp (ref "R34")
      (value "RESISTORRESISTOR/UPRIGHT/7.5")
      (footprint "eagle-import:RESISTOR_7.5")
      (libsource (lib "eagle-import") (part "RESISTORRESISTOR/UPRIGHT/7.5"))
    )
    (comp (ref "R35")
      (value "RESISTORRESISTOR/UPRIGHT/7.5")
      (footprint "eagle-import:RESISTOR_7.5")
      (libsource (lib "eagle-import") (part "RESISTORRESISTOR/UPRIGHT/7.5"))
    )
    (comp (ref "R36")
      (value "RESISTORRESISTOR/UPRIGHT/7.5")
      (footprint "eagle-import:RESISTOR_7.5")
      (libsource (lib "eagle-import") (part "RESISTORRESISTOR/UPRIGHT/7.5"))
    )
    (comp (ref "R37")
      (value "RESISTORRESISTOR/UPRIGHT/7.5")
      (footprint "eagle-import:RESISTOR_7.5")
      (libsource (lib "eagle-import") (part "RESISTORRESISTOR/UPRIGHT/7.5"))
    )
    (comp (ref "R38")
      (value "RESISTORRESISTOR/UPRIGHT/7.5")
      (footprint "eagle-import:RESISTOR_7.5")
      (libsource (lib "eagle-import") (part "RESISTORRESISTOR/UPRIGHT/7.5"))
    )
    (comp (ref "R39")
      (value "RESISTORRESISTOR/UPRIGHT/7.5")
      (footprint "eagle-import:RESISTOR_7.5")
      (libsource (lib "eagle-import") (part "RESISTORRESISTOR/UPRIGHT/7.5"))
    )
    (comp (ref "R40")
      (value "RESISTORRESISTOR/UPRIGHT/7.5")
      (footprint "eagle-import:RESISTOR_7.5")
      (libsource (lib "eagle-import") (part "RESISTORRESISTOR/UPRIGHT/7.5"))
    )
    (comp (ref "SCK")
      (value "HEADER/MALE/01")
      (footprint "eagle-import:HEADER_MALE_01")
      (fields (field (name "SPICEPREFIX") "X"))
      (libsource (lib "eagle-import") (part "HEADER/MALE/01"))
    )
  )
  (nets
    (net (code "1") (name "GND") (class "Default")
      (node (ref "GND") (pin "1") (pinfunction "3_1") (pintype "passive"))
      (node (ref "GND3") (pin "1") (pinfunction "3_1") (pintype "passive"))
      (node (ref "PIXI_GND") (pin "1") (pinfunction "3_1") (pintype "passive"))
      (node (ref "PIXI_GND1") (pin "1") (pinfunction "3_1") (pintype "passive"))
      (node (ref "PIXI_GND2") (pin "1") (pinfunction "3_1") (pintype "passive"))
      (node (ref "PIXI_GND3") (pin "1") (pinfunction "3_1") (pintype "passive"))
    )
    (net (code "2") (name "Net-(3.3V-3)") (class "Default")
      (node (ref "3.3V") (pin "1") (pinfunction "3_1") (pintype "passive"))
      (node (ref "3.3V1") (pin "1") (pinfunction "3_1") (pintype "passive"))
      (node (ref "PIXI_3.3V") (pin "1") (pinfunction "3_1") (pintype "passive"))
      (node (ref "PIXI_3.3V1") (pin "1") (pinfunction "3_1") (pintype "passive"))
    )
    (net (code "3") (name "Net-(5V-3)") (class "Default")
      (node (ref "5V") (pin "1") (pinfunction "3_1") (pintype "passive"))
      (node (ref "5V1") (pin "1") (pinfunction "3_1") (pintype "passive"))
      (node (ref "PIXI_5V") (pin "1") (pinfunction "3_1") (pintype "passive"))
      (node (ref "PIXI_5V1") (pin "1") (pinfunction "3_1") (pintype "passive"))
    )
    (net (code "4") (name "Net-(AVDDIO-3)") (class "Default")
      (node (ref "AVDDIO") (pin "1") (pinfunction "3_1") (pintype "passive"))
      (node (ref "AVDDIO1") (pin "1") (pinfunction "3_1") (pintype "passive"))
      (node (ref "AVDDIO2") (pin "1") (pinfunction "3_1") (pintype "passive"))
    )
    (net (code "5") (name "Net-(AVSSIO-3)") (class "Default")
      (node (ref "AVSSIO") (pin "1") (pinfunction "3_1") (pintype "passive"))
      (node (ref "AVSSIO1") (pin "1") (pinfunction "3_1") (pintype "passive"))
      (node (ref "AVSSIO2") (pin "1") (pinfunction "3_1") (pintype "passive"))
    )
    (net (code "6") (name "Net-(CNV-3)") (class "Default")
      (node (ref "CNV") (pin "1") (pinfunction "3_1") (pintype "passive"))
      (node (ref "PIXI_CNV") (pin "1") (pinfunction "3_1") (pintype "passive"))
      (node (ref "PIXI_CNV1") (pin "1") (pinfunction "3_1") (pintype "passive"))
    )
    (net (code "7") (name "Net-(CS1-3)") (class "Default")
      (node (ref "CS1") (pin "1") (pinfunction "3_1") (pintype "passive"))
      (node (ref "PIXI_CS") (pin "1") (pinfunction "3_1") (pintype "passive"))
    )
    (net (code "8") (name "Net-(CS2-3)") (class "Default")
      (node (ref "CS2") (pin "1") (pinfunction "3_1") (pintype "passive"))
      (node (ref "PIXI_CS1") (pin "1") (pinfunction "3_1") (pintype "passive"))
    )
    (net (code "9") (name "Net-(IO_0-3)") (class "Default")
      (node (ref "IO_0") (pin "1") (pinfunction "3_1") (pintype "passive"))
      (node (ref "R1") (pin "2") (pinfunction "2_2") (pintype "passive"))
    )
    (net (code "10") (name "Net-(IO_1-3)") (class "Default")
      (node (ref "IO_1") (pin "1") (pinfunction "3_1") (pintype "passive"))
      (node (ref "R2") (pin "2") (pinfunction "2_2") (pintype "passive"))
    )
    (net (code "11") (name "Net-(IO_2-3)") (class "Default")
      (node (ref "IO_2") (pin "1") (pinfunction "3_1") (pintype "passive"))
      (node (ref "R3") (pin "2") (pinfunction "2_2") (pintype "passive"))
    )
    (net (code "12") (name "Net-(IO_3-3)") (class "Default")
      (node (ref "IO_3") (pin "1") (pinfunction "3_1") (pintype "passive"))
      (node (ref "R4") (pin "2") (pinfunction "2_2") (pintype "passive"))
    )
    (net (code "13") (name "Net-(IO_4-3)") (class "Default")
      (node (ref "IO_4") (pin "1") (pinfunction "3_1") (pintype "passive"))
      (node (ref "R5") (pin "2") (pinfunction "2_2") (pintype "passive"))
    )
    (net (code "14") (name "Net-(IO_5-3)") (class "Default")
      (node (ref "IO_5") (pin "1") (pinfunction "3_1") (pintype "passive"))
      (node (ref "R6") (pin "2") (pinfunction "2_2") (pintype "passive"))
    )
    (net (code "15") (name "Net-(IO_6-3)") (class "Default")
      (node (ref "IO_6") (pin "1") (pinfunction "3_1") (pintype "passive"))
      (node (ref "R7") (pin "2") (pinfunction "2_2") (pintype "passive"))
    )
    (net (code "16") (name "Net-(IO_7-3)") (class "Default")
      (node (ref "IO_7") (pin "1") (pinfunction "3_1") (pintype "passive"))
      (node (ref "R8") (pin "2") (pinfunction "2_2") (pintype "passive"))
    )
    (net (code "17") (name "Net-(IO_8-3)") (class "Default")
      (node (ref "IO_8") (pin "1") (pinfunction "3_1") (pintype "passive"))
      (node (ref "R9") (pin "2") (pinfunction "2_2") (pintype "passive"))
    )
    (net (code "18") (name "Net-(IO_9-3)") (class "Default")
      (node (ref "IO_9") (pin "1") (pinfunction "3_1") (pintype "passive"))
      (node (ref "R10") (pin "2") (pinfunction "2_2") (pintype "passive"))
    )
    (net (code "19") (name "Net-(IO_10-3)") (class "Default")
      (node (ref "IO_10") (pin "1") (pinfunction "3_1") (pintype "passive"))
      (node (ref "R11") (pin "2") (pinfunction "2_2") (pintype "passive"))
    )
    (net (code "20") (name "Net-(IO_11-3)") (class "Default")
      (node (ref "IO_11") (pin "1") (pinfunction "3_1") (pintype "passive"))
      (node (ref "R12") (pin "2") (pinfunction "2_2") (pintype "passive"))
    )
    (net (code "21") (name "Net-(IO_12-3)") (class "Default")
      (node (ref "IO_12") (pin "1") (pinfunction "3_1") (pintype "passive"))
      (node (ref "R13") (pin "2") (pinfunction "2_2") (pintype "passive"))
    )
    (net (code "22") (name "Net-(IO_13-3)") (class "Default")
      (node (ref "IO_13") (pin "1") (pinfunction "3_1") (pintype "passive"))
      (node (ref "R14") (pin "2") (pinfunction "2_2") (pintype "passive"))
    )
    (net (code "23") (name "Net-(IO_14-3)") (class "Default")
      (node (ref "IO_14") (pin "1") (pinfunction "3_1") (pintype "passive"))
      (node (ref "R15") (pin "2") (pinfunction "2_2") (pintype "passive"))
    )
    (net (code "24") (name "Net-(IO_15-3)") (class "Default")
      (node (ref "IO_15") (pin "1") (pinfunction "3_1") (pintype "passive"))
      (node (ref "R16") (pin "2") (pinfunction "2_2") (pintype "passive"))
    )
    (net (code "25") (name "Net-(IO_16-3)") (class "Default")
      (node (ref "IO_16") (pin "1") (pinfunction "3_1") (pintype "passive"))
      (node (ref "R17") (pin "2") (pinfunction "2_2") (pintype "passive"))
    )
    (net (code "26") (name "Net-(IO_17-3)") (class "Default")
      (node (ref "IO_17") (pin "1") (pinfunction "3_1") (pintype "passive"))
      (node (ref "R18") (pin "2") (pinfunction "2_2") (pintype "passive"))
    )
    (net (code "27") (name "Net-(IO_18-3)") (class "Default")
      (node (ref "IO_18") (pin "1") (pinfunction "3_1") (pintype "passive"))
      (node (ref "R19") (pin "2") (pinfunction "2_2") (pintype "passive"))
    )
    (net (code "28") (name "Net-(IO_19-3)") (class "Default")
      (node (ref "IO_19") (pin "1") (pinfunction "3_1") (pintype "passive"))
      (node (ref "R20") (pin "2") (pinfunction "2_2") (pintype "passive"))
    )
    (net (code "29") (name "Net-(IO_20-3)") (class "Default")
      (node (ref "IO_20") (pin "1") (pinfunction "3_1") (pintype "passive"))
      (node (ref "R21") (pin "2") (pinfunction "2_2") (pintype "passive"))
    )
    (net (code "30") (name "Net-(IO_21-3)") (class "Default")
      (node (ref "IO_21") (pin "1") (pinfunction "3_1") (pintype "passive"))
      (node (ref "R22") (pin "2") (pinfunction "2_2") (pintype "passive"))
    )
    (net (code "31") (name "Net-(IO_22-3)") (class "Default")
      (node (ref "IO_22") (pin "1") (pinfunction "3_1") (pintype "passive"))
      (node (ref "R23") (pin "2") (pinfunction "2_2") (pintype "passive"))
    )
    (net (code "32") (name "Net-(IO_23-3)") (class "Default")
      (node (ref "IO_23") (pin "1") (pinfunction "3_1") (pintype "passive"))
      (node (ref "R24") (pin "2") (pinfunction "2_2") (pintype "passive"))
    )
    (net (code "33") (name "Net-(IO_24-3)") (class "Default")
      (node (ref "IO_24") (pin "1") (pinfunction "3_1") (pintype "passive"))
      (node (ref "R25") (pin "2") (pinfunction "2_2") (pintype "passive"))
    )
    (net (code "34") (name "Net-(IO_25-3)") (class "Default")
      (node (ref "IO_25") (pin "1") (pinfunction "3_1") (pintype "passive"))
      (node (ref "R26") (pin "2") (pinfunction "2_2") (pintype "passive"))
    )
    (net (code "35") (name "Net-(IO_26-3)") (class "Default")
      (node (ref "IO_26") (pin "1") (pinfunction "3_1") (pintype "passive"))
      (node (ref "R27") (pin "2") (pinfunction "2_2") (pintype "passive"))
    )
    (net (code "36") (name "Net-(IO_27-3)") (class "Default")
      (node (ref "IO_27") (pin "1") (pinfunction "3_1") (pintype "passive"))
      (node (ref "R28") (pin "2") (pinfunction "2_2") (pintype "passive"))
    )
    (net (code "37") (name "Net-(IO_28-3)") (class "Default")
      (node (ref "IO_28") (pin "1") (pinfunction "3_1") (pintype "passive"))
      (node (ref "R29") (pin "2") (pinfunction "2_2") (pintype "passive"))
    )
    (net (code "38") (name "Net-(IO_29-3)") (class "Default")
      (node (ref "IO_29") (pin "1") (pinfunction "3_1") (pintype "passive"))
      (node (ref "R30") (pin "2") (pinfunction "2_2") (pintype "passive"))
    )
    (net (code "39") (name "Net-(IO_30-3)") (class "Default")
      (node (ref "IO_30") (pin "1") (pinfunction "3_1") (pintype "passive"))
      (node (ref "R31") (pin "2") (pinfunction "2_2") (pintype "passive"))
    )
    (net (code "40") (name "Net-(IO_31-3)") (class "Default")
      (node (ref "IO_31") (pin "1") (pinfunction "3_1") (pintype "passive"))
      (node (ref "R32") (pin "2") (pinfunction "2_2") (pintype "passive"))
    )
    (net (code "41") (name "Net-(IO_32-3)") (class "Default")
      (node (ref "IO_32") (pin "1") (pinfunction "3_1") (pintype "passive"))
      (node (ref "R33") (pin "2") (pinfunction "2_2") (pintype "passive"))
    )
    (net (code "42") (name "Net-(IO_33-3)") (class "Default")
      (node (ref "IO_33") (pin "1") (pinfunction "3_1") (pintype "passive"))
      (node (ref "R34") (pin "2") (pinfunction "2_2") (pintype "passive"))
    )
    (net (code "43") (name "Net-(IO_34-3)") (class "Default")
      (node (ref "IO_34") (pin "1") (pinfunction "3_1") (pintype "passive"))
      (node (ref "R35") (pin "2") (pinfunction "2_2") (pintype "passive"))
    )
    (net (code "44") (name "Net-(IO_35-3)") (class "Default")
      (node (ref "IO_35") (pin "1") (pinfunction "3_1") (pintype "passive"))
      (node (ref "R36") (pin "2") (pinfunction "2_2") (pintype "passive"))
    )
    (net (code "45") (name "Net-(IO_36-3)") (class "Default")
      (node (ref "IO_36") (pin "1") (pinfunction "3_1") (pintype "passive"))
      (node (ref "R37") (pin "2") (pinfunction "2_2") (pintype "passive"))
    )
    (net (code "46") (name "Net-(IO_37-3)") (class "Default")
      (node (ref "IO_37") (pin "1") (pinfunction "3_1") (pintype "passive"))
      (node (ref "R38") (pin "2") (pinfunction "2_2") (pintype "passive"))
    )
    (net (code "47") (name "Net-(IO_38-3)") (class "Default")
      (node (ref "IO_38") (pin "1") (pinfunction "3_1") (pintype "passive"))
      (node (ref "R39") (pin "2") (pinfunction "2_2") (pintype "passive"))
    )
    (net (code "48") (name "Net-(IO_39-3)") (class "Default")
      (node (ref "IO_39") (pin "1") (pinfunction "3_1") (pintype "passive"))
      (node (ref "R40") (pin "2") (pinfunction "2_2") (pintype "passive"))
    )
    (net (code "49") (name "Net-(MISO-3)") (class "Default")
      (node (ref "MISO") (pin "1") (pinfunction "3_1") (pintype "passive"))
      (node (ref "PIXI_SDO") (pin "1") (pinfunction "3_1") (pintype "passive"))
      (node (ref "PIXI_SDO1") (pin "1") (pinfunction "3_1") (pintype "passive"))
    )
    (net (code "50") (name "Net-(MOSI-3)") (class "Default")
      (node (ref "MOSI") (pin "1") (pinfunction "3_1") (pintype "passive"))
      (node (ref "PIXI_SDI") (pin "1") (pinfunction "3_1") (pintype "passive"))
      (node (ref "PIXI_SDI1") (pin "1") (pinfunction "3_1") (pintype "passive"))
    )
    (net (code "51") (name "Net-(PIXI_0-3)") (class "Default")
      (node (ref "PIXI_0") (pin "1") (pinfunction "3_1") (pintype "passive"))
      (node (ref "R1") (pin "1") (pinfunction "1_1") (pintype "passive"))
    )
    (net (code "52") (name "Net-(PIXI_1-3)") (class "Default")
      (node (ref "PIXI_1") (pin "1") (pinfunction "3_1") (pintype "passive"))
      (node (ref "R2") (pin "1") (pinfunction "1_1") (pintype "passive"))
    )
    (net (code "53") (name "Net-(PIXI_2-3)") (class "Default")
      (node (ref "PIXI_2") (pin "1") (pinfunction "3_1") (pintype "passive"))
      (node (ref "R3") (pin "1") (pinfunction "1_1") (pintype "passive"))
    )
    (net (code "54") (name "Net-(PIXI_3-3)") (class "Default")
      (node (ref "PIXI_3") (pin "1") (pinfunction "3_1") (pintype "passive"))
      (node (ref "R4") (pin "1") (pinfunction "1_1") (pintype "passive"))
    )
    (net (code "55") (name "Net-(PIXI_4-3)") (class "Default")
      (node (ref "PIXI_4") (pin "1") (pinfunction "3_1") (pintype "passive"))
      (node (ref "R5") (pin "1") (pinfunction "1_1") (pintype "passive"))
    )
    (net (code "56") (name "Net-(PIXI_5-3)") (class "Default")
      (node (ref "PIXI_5") (pin "1") (pinfunction "3_1") (pintype "passive"))
      (node (ref "R6") (pin "1") (pinfunction "1_1") (pintype "passive"))
    )
    (net (code "57") (name "Net-(PIXI_6-3)") (class "Default")
      (node (ref "PIXI_6") (pin "1") (pinfunction "3_1") (pintype "passive"))
      (node (ref "R7") (pin "1") (pinfunction "1_1") (pintype "passive"))
    )
    (net (code "58") (name "Net-(PIXI_7-3)") (class "Default")
      (node (ref "PIXI_7") (pin "1") (pinfunction "3_1") (pintype "passive"))
      (node (ref "R8") (pin "1") (pinfunction "1_1") (pintype "passive"))
    )
    (net (code "59") (name "Net-(PIXI_8-3)") (class "Default")
      (node (ref "PIXI_8") (pin "1") (pinfunction "3_1") (pintype "passive"))
      (node (ref "R9") (pin "1") (pinfunction "1_1") (pintype "passive"))
    )
    (net (code "60") (name "Net-(PIXI_9-3)") (class "Default")
      (node (ref "PIXI_9") (pin "1") (pinfunction "3_1") (pintype "passive"))
      (node (ref "R10") (pin "1") (pinfunction "1_1") (pintype "passive"))
    )
    (net (code "61") (name "Net-(PIXI_10-3)") (class "Default")
      (node (ref "PIXI_10") (pin "1") (pinfunction "3_1") (pintype "passive"))
      (node (ref "R11") (pin "1") (pinfunction "1_1") (pintype "passive"))
    )
    (net (code "62") (name "Net-(PIXI_11-3)") (class "Default")
      (node (ref "PIXI_11") (pin "1") (pinfunction "3_1") (pintype "passive"))
      (node (ref "R12") (pin "1") (pinfunction "1_1") (pintype "passive"))
    )
    (net (code "63") (name "Net-(PIXI_12-3)") (class "Default")
      (node (ref "PIXI_12") (pin "1") (pinfunction "3_1") (pintype "passive"))
      (node (ref "R13") (pin "1") (pinfunction "1_1") (pintype "passive"))
    )
    (net (code "64") (name "Net-(PIXI_13-3)") (class "Default")
      (node (ref "PIXI_13") (pin "1") (pinfunction "3_1") (pintype "passive"))
      (node (ref "R14") (pin "1") (pinfunction "1_1") (pintype "passive"))
    )
    (net (code "65") (name "Net-(PIXI_14-3)") (class "Default")
      (node (ref "PIXI_14") (pin "1") (pinfunction "3_1") (pintype "passive"))
      (node (ref "R15") (pin "1") (pinfunction "1_1") (pintype "passive"))
    )
    (net (code "66") (name "Net-(PIXI_15-3)") (class "Default")
      (node (ref "PIXI_15") (pin "1") (pinfunction "3_1") (pintype "passive"))
      (node (ref "R16") (pin "1") (pinfunction "1_1") (pintype "passive"))
    )
    (net (code "67") (name "Net-(PIXI_16-3)") (class "Default")
      (node (ref "PIXI_16") (pin "1") (pinfunction "3_1") (pintype "passive"))
      (node (ref "R17") (pin "1") (pinfunction "1_1") (pintype "passive"))
    )
    (net (code "68") (name "Net-(PIXI_17-3)") (class "Default")
      (node (ref "PIXI_17") (pin "1") (pinfunction "3_1") (pintype "passive"))
      (node (ref "R18") (pin "1") (pinfunction "1_1") (pintype "passive"))
    )
    (net (code "69") (name "Net-(PIXI_18-3)") (class "Default")
      (node (ref "PIXI_18") (pin "1") (pinfunction "3_1") (pintype "passive"))
      (node (ref "R19") (pin "1") (pinfunction "1_1") (pintype "passive"))
    )
    (net (code "70") (name "Net-(PIXI_19-3)") (class "Default")
      (node (ref "PIXI_19") (pin "1") (pinfunction "3_1") (pintype "passive"))
      (node (ref "R20") (pin "1") (pinfunction "1_1") (pintype "passive"))
    )
    (net (code "71") (name "Net-(PIXI_20-3)") (class "Default")
      (node (ref "PIXI_20") (pin "1") (pinfunction "3_1") (pintype "passive"))
      (node (ref "R21") (pin "1") (pinfunction "1_1") (pintype "passive"))
    )
    (net (code "72") (name "Net-(PIXI_21-3)") (class "Default")
      (node (ref "PIXI_21") (pin "1") (pinfunction "3_1") (pintype "passive"))
      (node (ref "R22") (pin "1") (pinfunction "1_1") (pintype "passive"))
    )
    (net (code "73") (name "Net-(PIXI_22-3)") (class "Default")
      (node (ref "PIXI_22") (pin "1") (pinfunction "3_1") (pintype "passive"))
      (node (ref "R23") (pin "1") (pinfunction "1_1") (pintype "passive"))
    )
    (net (code "74") (name "Net-(PIXI_23-3)") (class "Default")
      (node (ref "PIXI_23") (pin "1") (pinfunction "3_1") (pintype "passive"))
      (node (ref "R24") (pin "1") (pinfunction "1_1") (pintype "passive"))
    )
    (net (code "75") (name "Net-(PIXI_24-3)") (class "Default")
      (node (ref "PIXI_24") (pin "1") (pinfunction "3_1") (pintype "passive"))
      (node (ref "R25") (pin "1") (pinfunction "1_1") (pintype "passive"))
    )
    (net (code "76") (name "Net-(PIXI_25-3)") (class "Default")
      (node (ref "PIXI_25") (pin "1") (pinfunction "3_1") (pintype "passive"))
      (node (ref "R26") (pin "1") (pinfunction "1_1") (pintype "passive"))
    )
    (net (code "77") (name "Net-(PIXI_26-3)") (class "Default")
      (node (ref "PIXI_26") (pin "1") (pinfunction "3_1") (pintype "passive"))
      (node (ref "R27") (pin "1") (pinfunction "1_1") (pintype "passive"))
    )
    (net (code "78") (name "Net-(PIXI_27-3)") (class "Default")
      (node (ref "PIXI_27") (pin "1") (pinfunction "3_1") (pintype "passive"))
      (node (ref "R28") (pin "1") (pinfunction "1_1") (pintype "passive"))
    )
    (net (code "79") (name "Net-(PIXI_28-3)") (class "Default")
      (node (ref "PIXI_28") (pin "1") (pinfunction "3_1") (pintype "passive"))
      (node (ref "R29") (pin "1") (pinfunction "1_1") (pintype "passive"))
    )
    (net (code "80") (name "Net-(PIXI_29-3)") (class "Default")
      (node (ref "PIXI_29") (pin "1") (pinfunction "3_1") (pintype "passive"))
      (node (ref "R30") (pin "1") (pinfunction "1_1") (pintype "passive"))
    )
    (net (code "81") (name "Net-(PIXI_30-3)") (class "Default")
      (node (ref "PIXI_30") (pin "1") (pinfunction "3_1") (pintype "passive"))
      (node (ref "R31") (pin "1") (pinfunction "1_1") (pintype "passive"))
    )
    (net (code "82") (name "Net-(PIXI_31-3)") (class "Default")
      (node (ref "PIXI_31") (pin "1") (pinfunction "3_1") (pintype "passive"))
      (node (ref "R32") (pin "1") (pinfunction "1_1") (pintype "passive"))
    )
    (net (code "83") (name "Net-(PIXI_32-3)") (class "Default")
      (node (ref "PIXI_32") (pin "1") (pinfunction "3_1") (pintype "passive"))
      (node (ref "R33") (pin "1") (pinfunction "1_1") (pintype "passive"))
    )
    (net (code "84") (name "Net-(PIXI_33-3)") (class "Default")
      (node (ref "PIXI_33") (pin "1") (pinfunction "3_1") (pintype "passive"))
      (node (ref "R34") (pin "1") (pinfunction "1_1") (pintype "passive"))
    )
    (net (code "85") (name "Net-(PIXI_34-3)") (class "Default")
      (node (ref "PIXI_34") (pin "1") (pinfunction "3_1") (pintype "passive"))
      (node (ref "R35") (pin "1") (pinfunction "1_1") (pintype "passive"))
    )
    (net (code "86") (name "Net-(PIXI_35-3)") (class "Default")
      (node (ref "PIXI_35") (pin "1") (pinfunction "3_1") (pintype "passive"))
      (node (ref "R36") (pin "1") (pinfunction "1_1") (pintype "passive"))
    )
    (net (code "87") (name "Net-(PIXI_36-3)") (class "Default")
      (node (ref "PIXI_36") (pin "1") (pinfunction "3_1") (pintype "passive"))
      (node (ref "R37") (pin "1") (pinfunction "1_1") (pintype "passive"))
    )
    (net (code "88") (name "Net-(PIXI_37-3)") (class "Default")
      (node (ref "PIXI_37") (pin "1") (pinfunction "3_1") (pintype "passive"))
      (node (ref "R38") (pin "1") (pinfunction "1_1") (pintype "passive"))
    )
    (net (code "89") (name "Net-(PIXI_38-3)") (class "Default")
      (node (ref "PIXI_38") (pin "1") (pinfunction "3_1") (pintype "passive"))
      (node (ref "R39") (pin "1") (pinfunction "1_1") (pintype "passive"))
    )
    (net (code "90") (name "Net-(PIXI_39-3)") (class "Default")
      (node (ref "PIXI_39") (pin "1") (pinfunction "3_1") (pintype "passive"))
      (node (ref "R40") (pin "1") (pinfunction "1_1") (pintype "passive"))
    )
    (net (code "91") (name "Net-(PIXI_SCK-3)") (class "Default")
      (node (ref "PIXI_SCK") (pin "1") (pinfunction "3_1") (pintype "passive"))
      (node (ref "PIXI_SCK1") (pin "1") (pinfunction "3_1") (pintype "passive"))
      (node (ref "SCK") (pin "1") (pinfunction "3_1") (pintype "passive"))
    )
    (net (code "92") (name "unconnected-(PIXI_INT-3-Pad1)") (class "Default")
      (node (ref "PIXI_INT") (pin "1") (pinfunction "3_1") (pintype "passive"))
    )
    (net (code "93") (name "unconnected-(PIXI_INT1-3-Pad1)") (class "Default")
      (node (ref "PIXI_INT1") (pin "1") (pinfunction "3_1") (pintype "passive"))
    )
    (net (code "94") (name "unconnected-(PIXI_NC1-3-Pad1)") (class "Default")
      (node (ref "PIXI_NC1") (pin "1") (pinfunction "3_1") (pintype "passive"))
    )
    (net (code "95") (name "unconnected-(PIXI_NC2-3-Pad1)") (class "Default")
      (node (ref "PIXI_NC2") (pin "1") (pinfunction "3_1") (pintype "passive"))
    )
    (net (code "96") (name "unconnected-(PIXI_NC3-3-Pad1)") (class "Default")
      (node (ref "PIXI_NC3") (pin "1") (pinfunction "3_1") (pintype "passive"))
    )
    (net (code "97") (name "unconnected-(PIXI_NC4-3-Pad1)") (class "Default")
      (node (ref "PIXI_NC4") (pin "1") (pinfunction "3_1") (pintype "passive"))
    )
    (net (code "98") (name "unconnected-(PIXI_NC5-3-Pad1)") (class "Default")
      (node (ref "PIXI_NC5") (pin "1") (pinfunction "3_1") (pintype "passive"))
    )
    (net (code "99") (name "unconnected-(PIXI_NC6-3-Pad1)") (class "Default")
      (node (ref "PIXI_NC6") (pin "1") (pinfunction "3_1") (pintype "passive"))
    )
    (net (code "100") (name "unconnected-(PIXI_NC7-3-Pad1)") (class "Default")
      (node (ref "PIXI_NC7") (pin "1") (pinfunction "3_1") (pintype "passive"))
    )
    (net (code "101") (name "unconnected-(PIXI_NC8-3-Pad1)") (class "Default")
      (node (ref "PIXI_NC8") (pin "1") (pinfunction "3_1") (pintype "passive"))
    )
    (net (code "102") (name "unconnected-(PIXI_NC9-3-Pad1)") (class "Default")
      (node (ref "PIXI_NC9") (pin "1") (pinfunction "3_1") (pintype "passive"))
    )
    (net (code "103") (name "unconnected-(PIXI_NC10-3-Pad1)") (class "Default")
      (node (ref "PIXI_NC10") (pin "1") (pinfunction "3_1") (pintype "passive"))
    )
    (net (code "104") (name "unconnected-(PIXI_NC11-3-Pad1)") (class "Default")
      (node (ref "PIXI_NC11") (pin "1") (pinfunction "3_1") (pintype "passive"))
    )
    (net (code "105") (name "unconnected-(PIXI_NC12-3-Pad1)") (class "Default")
      (node (ref "PIXI_NC12") (pin "1") (pinfunction "3_1") (pintype "passive"))
    )
  )
)
